# HiPowerProtect.net
KiCad netlist of a schematic drawn in Altium Designer
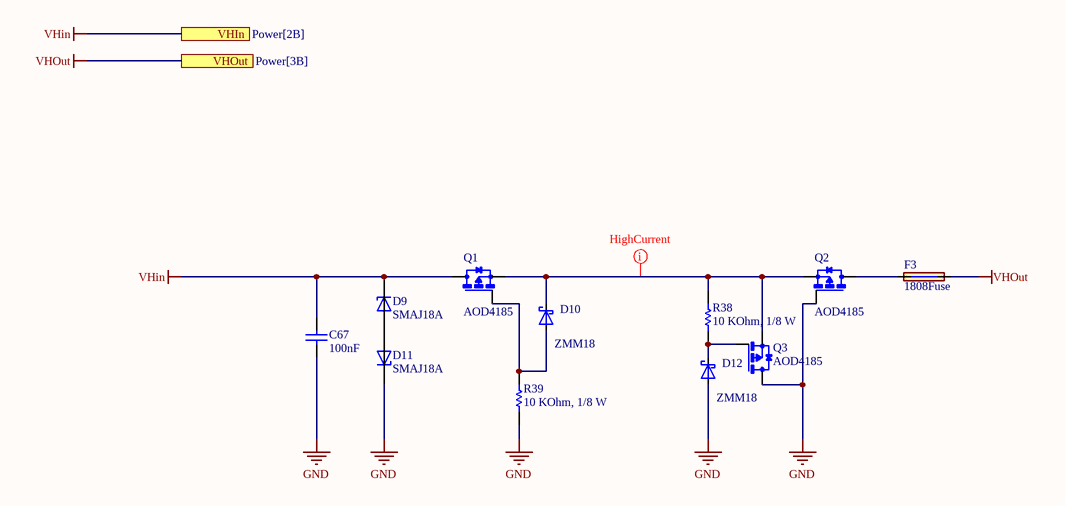
[diagram p0: HiPowerProtect.SchDoc]

(export (version "E")
  (design (tool "Eeschema 10.0.6"))
  (components
    (comp (ref "C67")
      (value "100nF")
      (footprint "CAP_0805")
      (description "CAP, size 0805, 0.1 nF, 50 VDC")
      (fields
        (field (name "TOLERANCE") "10%")
        (field (name "Comment") "0108051041050")
        (field (name "SOURCE") "Capacitor_0805_10_percent.SchLib")
      )
      (libsource (lib "Tin Tran") (part "0108056841050"))
    )
    (comp (ref "D9")
      (value "SMAJ18A")
      (footprint "DIOM4325X250N")
      (description "400W, 21.1V, 5%, Unidirectional, TVS")
      (fields (field (name "MF") "Taiwan Semiconductor"))
      (libsource (lib "Tin Tran") (part "SMAJ18A"))
    )
    (comp (ref "D10")
      (value "ZMM18")
      (footprint "SOD-80_MiniMELF_Glass")
      (libsource (lib "Tin Tran") (part "Schottky-Diode"))
    )
    (comp (ref "D11")
      (value "SMAJ18A")
      (footprint "DIOM4325X250N")
      (description "400W, 21.1V, 5%, Unidirectional, TVS")
      (fields (field (name "MF") "Taiwan Semiconductor"))
      (libsource (lib "Tin Tran") (part "SMAJ18A"))
    )
    (comp (ref "D12")
      (value "ZMM18")
      (footprint "SOD-80_MiniMELF_Glass")
      (libsource (lib "Tin Tran") (part "Schottky-Diode"))
    )
    (comp (ref "F3")
      (value "1808Fuse")
      (footprint "0154007.DR")
      (description "Fuse 1808 with case")
      (fields (field (name "MF") "Littelfuse Inc.") (field (name "MP") "0154007.DR"))
      (libsource (lib "Tin Tran") (part "0154007.DR"))
    )
    (comp (ref "Q1")
      (value "AOD4185")
      (footprint "DPAK")
      (description "P-Channel 40V 40A (Tc) 2.5W (Ta), 62.5W (Tc) Surface Mount TO-252, (D-Pak)")
      (fields (field (name "MF") "Alpha &"))
      (libsource (lib "") (part "AOD4185_1"))
    )
    (comp (ref "Q2")
      (value "AOD4185")
      (footprint "DPAK")
      (description "P-Channel 40V 40A (Tc) 2.5W (Ta), 62.5W (Tc) Surface Mount TO-252, (D-Pak)")
      (fields (field (name "MF") "Alpha &"))
      (libsource (lib "Tin Tran") (part "AOD4185"))
    )
    (comp (ref "Q3")
      (value "AOD4185")
      (footprint "DPAK")
      (description "P-Channel 40V 40A (Tc) 2.5W (Ta), 62.5W (Tc) Surface Mount TO-252, (D-Pak)")
      (fields (field (name "MF") "Alpha &"))
      (libsource (lib "") (part "AOD4185_1"))
    )
    (comp (ref "R38")
      (value "10 KOhm, 1/8 W")
      (footprint "RESISTOR_0805")
      (description "RES, size 0805, 10 KOhm, 1/8 W")
      (fields (field (name "Comment") "0008051031"))
      (libsource (lib "Tin Tran") (part "0008052035_1"))
    )
    (comp (ref "R39")
      (value "10 KOhm, 1/8 W")
      (footprint "RESISTOR_0805")
      (description "RES, size 0805, 10 KOhm, 1/8 W")
      (fields (field (name "Comment") "0008051031"))
      (libsource (lib "Tin Tran") (part "0008052035_1"))
    )
  )
  (nets
    (net (code "1") (name "GND") (class "Default")
      (node (ref "C67") (pin "1") (pinfunction "1_1") (pintype "passive"))
      (node (ref "D11") (pin "C") (pinfunction "C_C") (pintype "passive"))
      (node (ref "D12") (pin "A") (pinfunction "A_A") (pintype "passive"))
      (node (ref "Q2") (pin "1") (pinfunction "G_1") (pintype "passive"))
      (node (ref "Q3") (pin "4") (pinfunction "D_4") (pintype "passive"))
      (node (ref "R39") (pin "1") (pinfunction "1_1") (pintype "passive"))
    )
    (net (code "2") (name "Net-(D11-PadA)") (class "Default")
      (node (ref "D11") (pin "A") (pinfunction "A_A") (pintype "passive"))
      (node (ref "D9") (pin "A") (pinfunction "A_A") (pintype "passive"))
    )
    (net (code "3") (name "Net-(Q1-G)") (class "Default")
      (node (ref "D10") (pin "A") (pinfunction "A_A") (pintype "passive"))
      (node (ref "Q1") (pin "1") (pinfunction "G_1") (pintype "passive"))
      (node (ref "R39") (pin "2") (pinfunction "2_2") (pintype "passive"))
    )
    (net (code "4") (name "Net-(Q1-S)") (class "Default")
      (node (ref "D10") (pin "K") (pinfunction "K_K") (pintype "passive"))
      (node (ref "Q1") (pin "3") (pinfunction "S_3") (pintype "passive"))
      (node (ref "Q2") (pin "3") (pinfunction "S_3") (pintype "passive"))
      (node (ref "Q3") (pin "3") (pinfunction "S_3") (pintype "passive"))
      (node (ref "R38") (pin "2") (pinfunction "2_2") (pintype "passive"))
    )
    (net (code "5") (name "Net-(Q2-D)") (class "Default")
      (node (ref "F3") (pin "1") (pinfunction "1_1") (pintype "passive"))
      (node (ref "Q2") (pin "4") (pinfunction "D_4") (pintype "passive"))
    )
    (net (code "6") (name "Net-(Q3-G)") (class "Default")
      (node (ref "D12") (pin "K") (pinfunction "K_K") (pintype "passive"))
      (node (ref "Q3") (pin "1") (pinfunction "G_1") (pintype "passive"))
      (node (ref "R38") (pin "1") (pinfunction "1_1") (pintype "passive"))
    )
    (net (code "7") (name "VHOut") (class "Default")
      (node (ref "F3") (pin "2") (pinfunction "2_2") (pintype "passive"))
    )
    (net (code "8") (name "VHin") (class "Default")
      (node (ref "C67") (pin "2") (pinfunction "2_2") (pintype "passive"))
      (node (ref "D9") (pin "C") (pinfunction "C_C") (pintype "passive"))
      (node (ref "Q1") (pin "4") (pinfunction "D_4") (pintype "passive"))
    )
  )
)
